# AUDIO_CODEC.net
KiCad netlist of a schematic drawn in Altium Designer
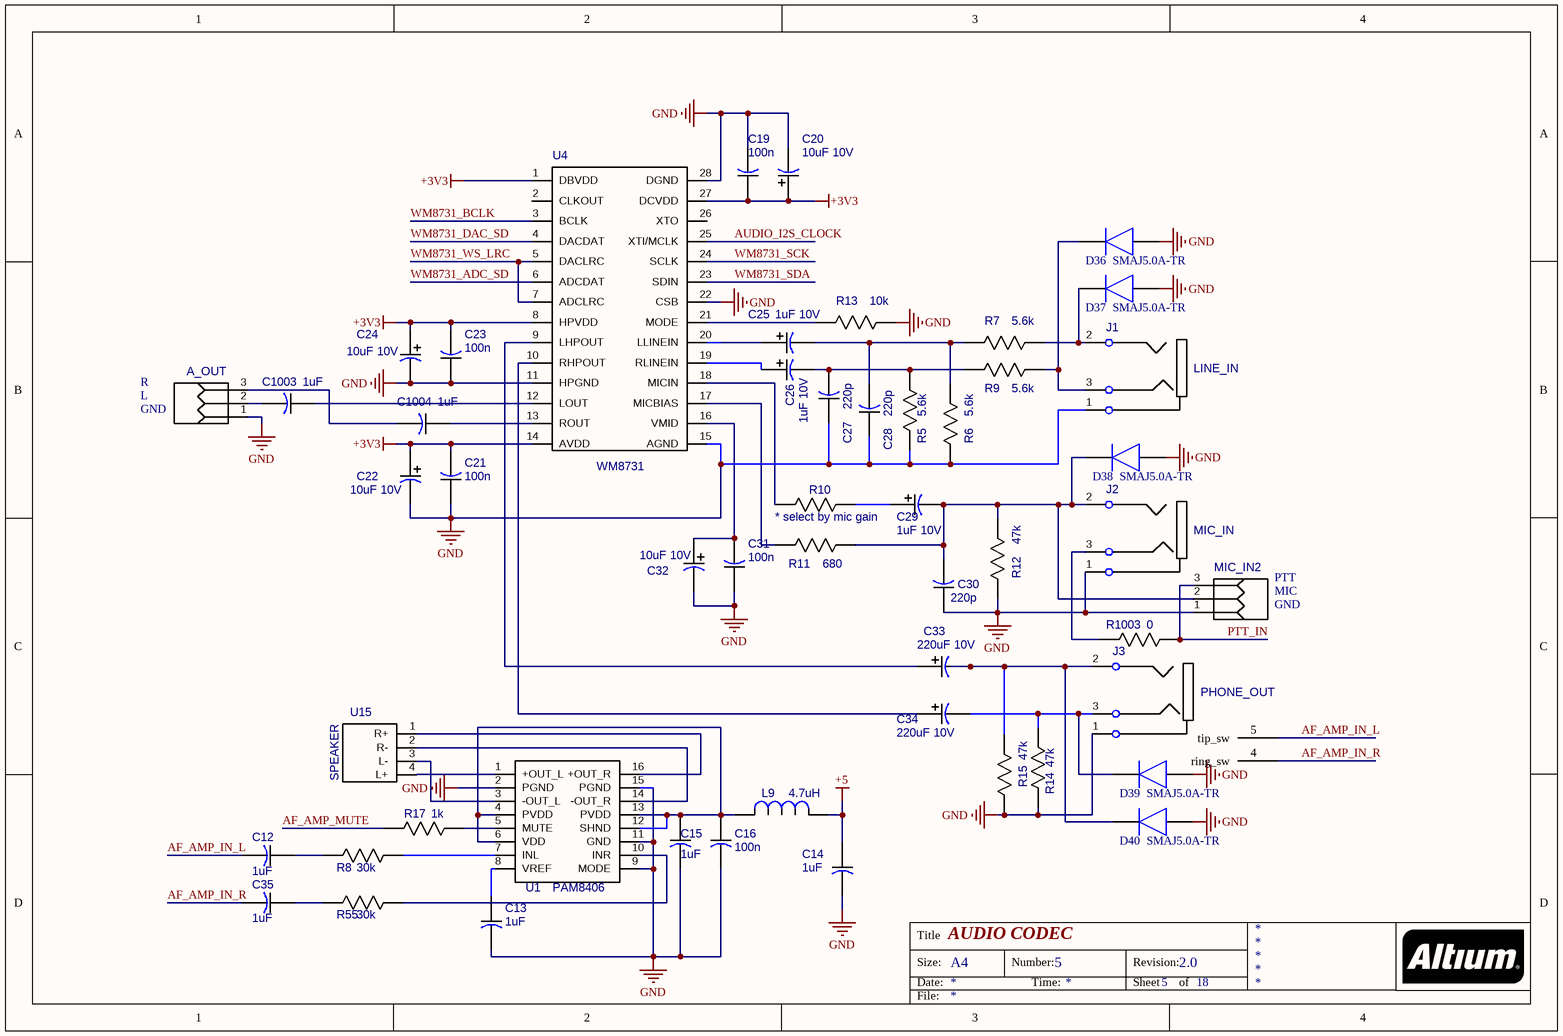
[diagram p0: AUDIO CODEC.SchDoc]

(export (version "E")
  (design (tool "Eeschema 10.0.6"))
  (components
    (comp (ref "A_OUT")
      (value "51022-0300_1")
      (footprint "51022-0200 - duplicate")
      (description "51022-0300")
      (libsource (lib "MOTHERBOARD") (part "51022-0300_1"))
    )
    (comp (ref "C12")
      (value "1uF")
      (footprint "CAP_0805")
      (description "CAP_0805")
      (libsource (lib "*") (part "CAP_0805"))
    )
    (comp (ref "C13")
      (value "1uF")
      (footprint "CAP_0805")
      (description "CAP_0805")
      (libsource (lib "*") (part "CAP_0805"))
    )
    (comp (ref "C14")
      (value "1uF")
      (footprint "CAP_0805")
      (description "CAP_0805")
      (libsource (lib "*") (part "CAP_0805"))
    )
    (comp (ref "C15")
      (value "1uF")
      (footprint "CAP_0805")
      (description "CAP_0805")
      (libsource (lib "*") (part "CAP_0805"))
    )
    (comp (ref "C16")
      (value "100n")
      (footprint "CAP_0805")
      (description "CAP_0805")
      (libsource (lib "*") (part "CAP_0805"))
    )
    (comp (ref "C19")
      (value "100n")
      (footprint "CAP_0805")
      (description "CAP_0805")
      (libsource (lib "*") (part "CAP_0805"))
    )
    (comp (ref "C20")
      (value "10uF 10V")
      (footprint "CAPAE_4.3x4.3h5.4")
      (description "CAPAE_4.3x4.3h5.4")
      (libsource (lib "*") (part "CAPAE_4.3x4.3h5.4"))
    )
    (comp (ref "C21")
      (value "100n")
      (footprint "CAP_0805")
      (description "CAP_0805")
      (libsource (lib "*") (part "CAP_0805"))
    )
    (comp (ref "C22")
      (value "10uF 10V")
      (footprint "CAPAE_4.3x4.3h5.4")
      (description "CAPAE_4.3x4.3h5.4")
      (libsource (lib "*") (part "CAPAE_4.3x4.3h5.4"))
    )
    (comp (ref "C23")
      (value "100n")
      (footprint "CAP_0805")
      (description "CAP_0805")
      (libsource (lib "*") (part "CAP_0805"))
    )
    (comp (ref "C24")
      (value "10uF 10V")
      (footprint "CAPAE_4.3x4.3h5.4")
      (description "CAPAE_4.3x4.3h5.4")
      (libsource (lib "*") (part "CAPAE_4.3x4.3h5.4"))
    )
    (comp (ref "C25")
      (value "1uF 10V")
      (footprint "CAPAE_4.3x4.3h5.4")
      (description "CAPAE_4.3x4.3h5.4")
      (libsource (lib "*") (part "CAPAE_4.3x4.3h5.4"))
    )
    (comp (ref "C26")
      (value "1uF 10V")
      (footprint "CAPAE_4.3x4.3h5.4")
      (description "CAPAE_4.3x4.3h5.4")
      (libsource (lib "*") (part "CAPAE_4.3x4.3h5.4"))
    )
    (comp (ref "C27")
      (value "220p")
      (footprint "CAP_0805")
      (description "CAP_0805")
      (libsource (lib "*") (part "CAP_0805"))
    )
    (comp (ref "C28")
      (value "220p")
      (footprint "CAP_0805")
      (description "CAP_0805")
      (libsource (lib "*") (part "CAP_0805"))
    )
    (comp (ref "C29")
      (value "1uF 10V")
      (footprint "CAPAE_4.3x4.3h5.4")
      (description "CAPAE_4.3x4.3h5.4")
      (libsource (lib "*") (part "CAPAE_4.3x4.3h5.4"))
    )
    (comp (ref "C30")
      (value "220p")
      (footprint "CAP_0805")
      (description "CAP_0805")
      (libsource (lib "*") (part "CAP_0805"))
    )
    (comp (ref "C31")
      (value "100n")
      (footprint "CAP_0805")
      (description "CAP_0805")
      (libsource (lib "*") (part "CAP_0805"))
    )
    (comp (ref "C32")
      (value "10uF 10V")
      (footprint "CAPAE_4.3x4.3h5.4")
      (description "CAPAE_4.3x4.3h5.4")
      (libsource (lib "*") (part "CAPAE_4.3x4.3h5.4"))
    )
    (comp (ref "C33")
      (value "220uF 10V")
      (footprint "EEEFC_sizeС")
      (description "CAPAE_4.3x4.3h5.4")
      (libsource (lib "*") (part "CAPAE_4.3x4.3h5.4"))
    )
    (comp (ref "C34")
      (value "220uF 10V")
      (footprint "EEEFC_sizeС")
      (description "CAPAE_4.3x4.3h5.4")
      (libsource (lib "*") (part "CAPAE_4.3x4.3h5.4"))
    )
    (comp (ref "C35")
      (value "1uF")
      (footprint "CAP_0805")
      (description "CAP_0805")
      (libsource (lib "*") (part "CAP_0805"))
    )
    (comp (ref "C1003")
      (value "1uF")
      (footprint "CAP_0805")
      (description "CAP_0805")
      (libsource (lib "*") (part "CAP_0805"))
    )
    (comp (ref "C1004")
      (value "1uF")
      (footprint "CAP_0805")
      (description "CAP_0805")
      (libsource (lib "*") (part "CAP_0805"))
    )
    (comp (ref "D36")
      (value "SMAJ5.0A-TR")
      (footprint "SamacSys:SMBJ36CATR")
      (description "Diode")
      (fields
        (field (name "MANUFACTURER_PART_NUMBER") "SMLVT3V3")
        (field (name "MOUSER PART NUMBER") "511-SMLVT3V3")
      )
      (libsource (lib "*") (part "SMLVT3V3"))
    )
    (comp (ref "D37")
      (value "SMAJ5.0A-TR")
      (footprint "SamacSys:SMBJ36CATR")
      (description "Diode")
      (fields
        (field (name "MANUFACTURER_PART_NUMBER") "SMLVT3V3")
        (field (name "MOUSER PART NUMBER") "511-SMLVT3V3")
      )
      (libsource (lib "*") (part "SMLVT3V3"))
    )
    (comp (ref "D38")
      (value "SMAJ5.0A-TR")
      (footprint "SamacSys:SMBJ36CATR")
      (description "Diode")
      (fields
        (field (name "MANUFACTURER_PART_NUMBER") "SMLVT3V3")
        (field (name "MOUSER PART NUMBER") "511-SMLVT3V3")
      )
      (libsource (lib "*") (part "SMLVT3V3"))
    )
    (comp (ref "D39")
      (value "SMAJ5.0A-TR")
      (footprint "SamacSys:SMBJ36CATR")
      (description "Diode")
      (fields
        (field (name "MANUFACTURER_PART_NUMBER") "SMLVT3V3")
        (field (name "MOUSER PART NUMBER") "511-SMLVT3V3")
      )
      (libsource (lib "*") (part "SMLVT3V3"))
    )
    (comp (ref "D40")
      (value "SMAJ5.0A-TR")
      (footprint "SamacSys:SMBJ36CATR")
      (description "Diode")
      (fields
        (field (name "MANUFACTURER_PART_NUMBER") "SMLVT3V3")
        (field (name "MOUSER PART NUMBER") "511-SMLVT3V3")
      )
      (libsource (lib "*") (part "SMLVT3V3"))
    )
    (comp (ref "J1")
      (value "LINE_IN")
      (footprint "SJ1-3525NG")
      (description "SJ1-3525NG")
      (libsource (lib "*") (part "SJ1-3523N"))
    )
    (comp (ref "J2")
      (value "MIC_IN")
      (footprint "SJ1-3525NG")
      (description "SJ1-3525NG")
      (libsource (lib "*") (part "SJ1-3523N"))
    )
    (comp (ref "J3")
      (value "PHONE_OUT")
      (footprint "SJ1-3525NG")
      (description "SJ1-3525NG")
      (libsource (lib "") (part "SJ1-3523N_1"))
    )
    (comp (ref "L9")
      (value "4.7uH")
      (footprint "IND_1812")
      (description "IND_1812")
      (fields (field (name "Comment") "3.3uH"))
      (libsource (lib "*") (part "IND_1812"))
    )
    (comp (ref "MIC_IN2")
      (value "51022-0300_1")
      (footprint "51022-0200 - duplicate")
      (description "51022-0300")
      (libsource (lib "MOTHERBOARD") (part "51022-0300_1"))
    )
    (comp (ref "R5")
      (value "5.6k")
      (footprint "RES_0805")
      (description "RES_0805")
      (libsource (lib "*") (part "RES_0805"))
    )
    (comp (ref "R6")
      (value "5.6k")
      (footprint "RES_0805")
      (description "RES_0805")
      (libsource (lib "*") (part "RES_0805"))
    )
    (comp (ref "R7")
      (value "5.6k")
      (footprint "RES_0805")
      (description "RES_0805")
      (libsource (lib "*") (part "RES_0805"))
    )
    (comp (ref "R8")
      (value "30k")
      (footprint "RES_0805")
      (description "RES_0805")
      (libsource (lib "*") (part "RES_0805"))
    )
    (comp (ref "R9")
      (value "5.6k")
      (footprint "RES_0805")
      (description "RES_0805")
      (libsource (lib "*") (part "RES_0805"))
    )
    (comp (ref "R10")
      (value "* select by mic gain")
      (footprint "RES_0805")
      (description "RES_0805")
      (libsource (lib "*") (part "RES_0805"))
    )
    (comp (ref "R11")
      (value "680")
      (footprint "RES_0805")
      (description "RES_0805")
      (libsource (lib "*") (part "RES_0805"))
    )
    (comp (ref "R12")
      (value "47k")
      (footprint "RES_0805")
      (description "RES_0805")
      (libsource (lib "*") (part "RES_0805"))
    )
    (comp (ref "R13")
      (value "10k")
      (footprint "RES_0805")
      (description "RES_0805")
      (libsource (lib "*") (part "RES_0805"))
    )
    (comp (ref "R14")
      (value "47k")
      (footprint "RES_0805")
      (description "RES_0805")
      (libsource (lib "*") (part "RES_0805"))
    )
    (comp (ref "R15")
      (value "47k")
      (footprint "RES_0805")
      (description "RES_0805")
      (libsource (lib "*") (part "RES_0805"))
    )
    (comp (ref "R17")
      (value "1k")
      (footprint "RES_0805")
      (description "RES_0805")
      (libsource (lib "*") (part "RES_0805"))
    )
    (comp (ref "R55")
      (value "30k")
      (footprint "RES_0805")
      (description "RES_0805")
      (libsource (lib "*") (part "RES_0805"))
    )
    (comp (ref "R1003")
      (value "0")
      (footprint "RES_0805")
      (description "RES_0805")
      (libsource (lib "*") (part "RES_0805"))
    )
    (comp (ref "U1") (value "PAM8406") (footprint "PAM8403") (libsource (lib "MOTHERBOARD") (part "PAM8406")))
    (comp (ref "U4") (value "WM8731") (footprint "WM8731") (libsource (lib "*") (part "WM8731")))
    (comp (ref "U15")
      (value "SPEAKER")
      (footprint "speaker conn")
      (description "4 pins conn")
      (libsource (lib "MOTHERBOARD") (part "speaker conn"))
    )
  )
  (nets
    (net (code "1") (name "+3V3") (class "Default")
      (node (ref "C19") (pin "1") (pinfunction "1_1") (pintype "passive"))
      (node (ref "C20") (pin "1") (pinfunction "PLUS_1") (pintype "passive"))
      (node (ref "C21") (pin "2") (pinfunction "2_2") (pintype "passive"))
      (node (ref "C22") (pin "1") (pinfunction "PLUS_1") (pintype "passive"))
      (node (ref "C23") (pin "2") (pinfunction "2_2") (pintype "passive"))
      (node (ref "C24") (pin "1") (pinfunction "PLUS_1") (pintype "passive"))
      (node (ref "U4") (pin "1") (pinfunction "DBVDD_1") (pintype "passive"))
      (node (ref "U4") (pin "14") (pinfunction "AVDD_14") (pintype "passive"))
      (node (ref "U4") (pin "27") (pinfunction "DCVDD_27") (pintype "passive"))
      (node (ref "U4") (pin "8") (pinfunction "HPVDD_8") (pintype "passive"))
    )
    (net (code "2") (name "+5") (class "Default")
      (node (ref "C14") (pin "1") (pinfunction "1_1") (pintype "passive"))
      (node (ref "L9") (pin "2") (pinfunction "2_2") (pintype "passive"))
    )
    (net (code "3") (name "/AF_AMP_IN_L") (class "Default")
      (node (ref "C12") (pin "2") (pinfunction "2_2") (pintype "passive"))
      (node (ref "J3") (pin "5") (pinfunction "tip_sw_5") (pintype "passive"))
    )
    (net (code "4") (name "/AF_AMP_IN_R") (class "Default")
      (node (ref "C35") (pin "2") (pinfunction "2_2") (pintype "passive"))
      (node (ref "J3") (pin "4") (pinfunction "ring_sw_4") (pintype "passive"))
    )
    (net (code "5") (name "/AF_AMP_MUTE") (class "Default")
      (node (ref "R17") (pin "2") (pinfunction "2_2") (pintype "passive"))
    )
    (net (code "6") (name "/AUDIO_I2S_CLOCK") (class "Default")
      (node (ref "U4") (pin "25") (pinfunction "XTI/MCLK_25") (pintype "passive"))
    )
    (net (code "7") (name "/PTT_IN") (class "Default")
      (node (ref "MIC_IN2") (pin "3") (pintype "passive"))
      (node (ref "R1003") (pin "2") (pinfunction "2_2") (pintype "passive"))
    )
    (net (code "8") (name "/WM8731_ADC_SD") (class "Default")
      (node (ref "U4") (pin "6") (pinfunction "ADCDAT_6") (pintype "passive"))
    )
    (net (code "9") (name "/WM8731_BCLK") (class "Default")
      (node (ref "U4") (pin "3") (pinfunction "BCLK_3") (pintype "passive"))
    )
    (net (code "10") (name "/WM8731_DAC_SD") (class "Default")
      (node (ref "U4") (pin "4") (pinfunction "DACDAT_4") (pintype "passive"))
    )
    (net (code "11") (name "/WM8731_SCK") (class "Default")
      (node (ref "U4") (pin "24") (pinfunction "SCLK_24") (pintype "passive"))
    )
    (net (code "12") (name "/WM8731_SDA") (class "Default")
      (node (ref "U4") (pin "23") (pinfunction "SDIN_23") (pintype "passive"))
    )
    (net (code "13") (name "/WM8731_WS_LRC") (class "Default")
      (node (ref "U4") (pin "5") (pinfunction "DACLRC_5") (pintype "passive"))
      (node (ref "U4") (pin "7") (pinfunction "ADCLRC_7") (pintype "passive"))
    )
    (net (code "14") (name "GND") (class "Default")
      (node (ref "A_OUT") (pin "1") (pintype "passive"))
      (node (ref "C13") (pin "2") (pinfunction "2_2") (pintype "passive"))
      (node (ref "C14") (pin "2") (pinfunction "2_2") (pintype "passive"))
      (node (ref "C15") (pin "2") (pinfunction "2_2") (pintype "passive"))
      (node (ref "C16") (pin "2") (pinfunction "2_2") (pintype "passive"))
      (node (ref "C19") (pin "2") (pinfunction "2_2") (pintype "passive"))
      (node (ref "C20") (pin "2") (pinfunction "MINUS_2") (pintype "passive"))
      (node (ref "C21") (pin "1") (pinfunction "1_1") (pintype "passive"))
      (node (ref "C22") (pin "2") (pinfunction "MINUS_2") (pintype "passive"))
      (node (ref "C23") (pin "1") (pinfunction "1_1") (pintype "passive"))
      (node (ref "C24") (pin "2") (pinfunction "MINUS_2") (pintype "passive"))
      (node (ref "C27") (pin "1") (pinfunction "1_1") (pintype "passive"))
      (node (ref "C28") (pin "1") (pinfunction "1_1") (pintype "passive"))
      (node (ref "C30") (pin "1") (pinfunction "1_1") (pintype "passive"))
      (node (ref "C31") (pin "1") (pinfunction "1_1") (pintype "passive"))
      (node (ref "C32") (pin "2") (pinfunction "MINUS_2") (pintype "passive"))
      (node (ref "D36") (pin "2") (pinfunction "A_2") (pintype "passive"))
      (node (ref "D37") (pin "2") (pinfunction "A_2") (pintype "passive"))
      (node (ref "D38") (pin "2") (pinfunction "A_2") (pintype "passive"))
      (node (ref "D39") (pin "2") (pinfunction "A_2") (pintype "passive"))
      (node (ref "D40") (pin "2") (pinfunction "A_2") (pintype "passive"))
      (node (ref "J1") (pin "1") (pinfunction "sleeve_1") (pintype "passive"))
      (node (ref "J2") (pin "1") (pinfunction "sleeve_1") (pintype "passive"))
      (node (ref "J3") (pin "1") (pinfunction "sleeve_1") (pintype "passive"))
      (node (ref "MIC_IN2") (pin "1") (pintype "passive"))
      (node (ref "R12") (pin "1") (pinfunction "1_1") (pintype "passive"))
      (node (ref "R13") (pin "1") (pinfunction "1_1") (pintype "passive"))
      (node (ref "R14") (pin "1") (pinfunction "1_1") (pintype "passive"))
      (node (ref "R15") (pin "1") (pinfunction "1_1") (pintype "passive"))
      (node (ref "R5") (pin "1") (pinfunction "1_1") (pintype "passive"))
      (node (ref "R6") (pin "1") (pinfunction "1_1") (pintype "passive"))
      (node (ref "U1") (pin "11") (pinfunction "GND_11") (pintype "passive"))
      (node (ref "U1") (pin "15") (pinfunction "PGND_15") (pintype "passive"))
      (node (ref "U1") (pin "2") (pinfunction "PGND_2") (pintype "passive"))
      (node (ref "U1") (pin "9") (pinfunction "MODE_9") (pintype "passive"))
      (node (ref "U4") (pin "11") (pinfunction "HPGND_11") (pintype "passive"))
      (node (ref "U4") (pin "15") (pinfunction "AGND_15") (pintype "passive"))
      (node (ref "U4") (pin "22") (pinfunction "CSB_22") (pintype "passive"))
      (node (ref "U4") (pin "28") (pinfunction "DGND_28") (pintype "passive"))
    )
    (net (code "15") (name "Net-(A_OUT-Pad2)") (class "Default")
      (node (ref "A_OUT") (pin "2") (pintype "passive"))
      (node (ref "C1003") (pin "2") (pinfunction "2_2") (pintype "passive"))
    )
    (net (code "16") (name "Net-(A_OUT-Pad3)") (class "Default")
      (node (ref "A_OUT") (pin "3") (pintype "passive"))
      (node (ref "C1004") (pin "2") (pinfunction "2_2") (pintype "passive"))
    )
    (net (code "17") (name "Net-(C12-Pad1)") (class "Default")
      (node (ref "C12") (pin "1") (pinfunction "1_1") (pintype "passive"))
      (node (ref "R8") (pin "2") (pinfunction "2_2") (pintype "passive"))
    )
    (net (code "18") (name "Net-(C25-MINUS)") (class "Default")
      (node (ref "C25") (pin "2") (pinfunction "MINUS_2") (pintype "passive"))
      (node (ref "C28") (pin "2") (pinfunction "2_2") (pintype "passive"))
      (node (ref "R6") (pin "2") (pinfunction "2_2") (pintype "passive"))
      (node (ref "R7") (pin "2") (pinfunction "2_2") (pintype "passive"))
    )
    (net (code "19") (name "Net-(C25-PLUS)") (class "Default")
      (node (ref "C25") (pin "1") (pinfunction "PLUS_1") (pintype "passive"))
      (node (ref "U4") (pin "20") (pinfunction "LLINEIN_20") (pintype "passive"))
    )
    (net (code "20") (name "Net-(C26-MINUS)") (class "Default")
      (node (ref "C26") (pin "2") (pinfunction "MINUS_2") (pintype "passive"))
      (node (ref "C27") (pin "2") (pinfunction "2_2") (pintype "passive"))
      (node (ref "R5") (pin "2") (pinfunction "2_2") (pintype "passive"))
      (node (ref "R9") (pin "2") (pinfunction "2_2") (pintype "passive"))
    )
    (net (code "21") (name "Net-(C26-PLUS)") (class "Default")
      (node (ref "C26") (pin "1") (pinfunction "PLUS_1") (pintype "passive"))
      (node (ref "U4") (pin "19") (pinfunction "RLINEIN_19") (pintype "passive"))
    )
    (net (code "22") (name "Net-(C29-MINUS)") (class "Default")
      (node (ref "C29") (pin "2") (pinfunction "MINUS_2") (pintype "passive"))
      (node (ref "C30") (pin "2") (pinfunction "2_2") (pintype "passive"))
      (node (ref "D38") (pin "1") (pinfunction "K_1") (pintype "passive"))
      (node (ref "J2") (pin "2") (pinfunction "tip_2") (pintype "passive"))
      (node (ref "MIC_IN2") (pin "2") (pintype "passive"))
      (node (ref "R11") (pin "1") (pinfunction "1_1") (pintype "passive"))
      (node (ref "R12") (pin "2") (pinfunction "2_2") (pintype "passive"))
    )
    (net (code "23") (name "Net-(C29-PLUS)") (class "Default")
      (node (ref "C29") (pin "1") (pinfunction "PLUS_1") (pintype "passive"))
      (node (ref "R10") (pin "1") (pinfunction "1_1") (pintype "passive"))
    )
    (net (code "24") (name "Net-(C32-PLUS)") (class "Default")
      (node (ref "C31") (pin "2") (pinfunction "2_2") (pintype "passive"))
      (node (ref "C32") (pin "1") (pinfunction "PLUS_1") (pintype "passive"))
      (node (ref "U4") (pin "16") (pinfunction "VMID_16") (pintype "passive"))
    )
    (net (code "25") (name "Net-(C33-MINUS)") (class "Default")
      (node (ref "C33") (pin "2") (pinfunction "MINUS_2") (pintype "passive"))
      (node (ref "D40") (pin "1") (pinfunction "K_1") (pintype "passive"))
      (node (ref "J3") (pin "2") (pinfunction "tip_2") (pintype "passive"))
      (node (ref "R15") (pin "2") (pinfunction "2_2") (pintype "passive"))
    )
    (net (code "26") (name "Net-(C33-PLUS)") (class "Default")
      (node (ref "C33") (pin "1") (pinfunction "PLUS_1") (pintype "passive"))
      (node (ref "U4") (pin "9") (pinfunction "LHPOUT_9") (pintype "passive"))
    )
    (net (code "27") (name "Net-(C34-MINUS)") (class "Default")
      (node (ref "C34") (pin "2") (pinfunction "MINUS_2") (pintype "passive"))
      (node (ref "D39") (pin "1") (pinfunction "K_1") (pintype "passive"))
      (node (ref "J3") (pin "3") (pinfunction "ring_3") (pintype "passive"))
      (node (ref "R14") (pin "2") (pinfunction "2_2") (pintype "passive"))
    )
    (net (code "28") (name "Net-(C34-PLUS)") (class "Default")
      (node (ref "C34") (pin "1") (pinfunction "PLUS_1") (pintype "passive"))
      (node (ref "U4") (pin "10") (pinfunction "RHPOUT_10") (pintype "passive"))
    )
    (net (code "29") (name "Net-(C35-Pad1)") (class "Default")
      (node (ref "C35") (pin "1") (pinfunction "1_1") (pintype "passive"))
      (node (ref "R55") (pin "2") (pinfunction "2_2") (pintype "passive"))
    )
    (net (code "30") (name "Net-(D36-K)") (class "Default")
      (node (ref "D36") (pin "1") (pinfunction "K_1") (pintype "passive"))
      (node (ref "J1") (pin "3") (pinfunction "ring_3") (pintype "passive"))
      (node (ref "R9") (pin "1") (pinfunction "1_1") (pintype "passive"))
    )
    (net (code "31") (name "Net-(D37-K)") (class "Default")
      (node (ref "D37") (pin "1") (pinfunction "K_1") (pintype "passive"))
      (node (ref "J1") (pin "2") (pinfunction "tip_2") (pintype "passive"))
      (node (ref "R7") (pin "1") (pinfunction "1_1") (pintype "passive"))
    )
    (net (code "32") (name "Net-(J2-ring)") (class "Default")
      (node (ref "J2") (pin "3") (pinfunction "ring_3") (pintype "passive"))
      (node (ref "R1003") (pin "1") (pinfunction "1_1") (pintype "passive"))
    )
    (net (code "33") (name "Net-(U1-+OUT_L)") (class "Default")
      (node (ref "U1") (pin "1") (pinfunction "+OUT_L_1") (pintype "passive"))
      (node (ref "U15") (pin "4") (pinfunction "L+_4") (pintype "passive"))
    )
    (net (code "34") (name "Net-(U1-+OUT_R)") (class "Default")
      (node (ref "U1") (pin "16") (pinfunction "+OUT_R_16") (pintype "passive"))
      (node (ref "U15") (pin "1") (pinfunction "R+_1") (pintype "passive"))
    )
    (net (code "35") (name "Net-(U1--OUT_L)") (class "Default")
      (node (ref "U1") (pin "3") (pinfunction "-OUT_L_3") (pintype "passive"))
      (node (ref "U15") (pin "3") (pinfunction "L-_3") (pintype "passive"))
    )
    (net (code "36") (name "Net-(U1--OUT_R)") (class "Default")
      (node (ref "U1") (pin "14") (pinfunction "-OUT_R_14") (pintype "passive"))
      (node (ref "U15") (pin "2") (pinfunction "R-_2") (pintype "passive"))
    )
    (net (code "37") (name "Net-(U1-INL)") (class "Default")
      (node (ref "R8") (pin "1") (pinfunction "1_1") (pintype "passive"))
      (node (ref "U1") (pin "7") (pinfunction "INL_7") (pintype "passive"))
    )
    (net (code "38") (name "Net-(U1-INR)") (class "Default")
      (node (ref "R55") (pin "1") (pinfunction "1_1") (pintype "passive"))
      (node (ref "U1") (pin "10") (pinfunction "INR_10") (pintype "passive"))
    )
    (net (code "39") (name "Net-(U1-MUTE)") (class "Default")
      (node (ref "R17") (pin "1") (pinfunction "1_1") (pintype "passive"))
      (node (ref "U1") (pin "5") (pinfunction "MUTE_5") (pintype "passive"))
    )
    (net (code "40") (name "Net-(U1-SHND)") (class "Default")
      (node (ref "C15") (pin "1") (pinfunction "1_1") (pintype "passive"))
      (node (ref "C16") (pin "1") (pinfunction "1_1") (pintype "passive"))
      (node (ref "L9") (pin "1") (pinfunction "1_1") (pintype "passive"))
      (node (ref "U1") (pin "12") (pinfunction "SHND_12") (pintype "passive"))
      (node (ref "U1") (pin "13") (pinfunction "PVDD_13") (pintype "passive"))
      (node (ref "U1") (pin "4") (pinfunction "PVDD_4") (pintype "passive"))
      (node (ref "U1") (pin "6") (pinfunction "VDD_6") (pintype "passive"))
    )
    (net (code "41") (name "Net-(U1-VREF)") (class "Default")
      (node (ref "C13") (pin "1") (pinfunction "1_1") (pintype "passive"))
      (node (ref "U1") (pin "8") (pinfunction "VREF_8") (pintype "passive"))
    )
    (net (code "42") (name "Net-(U4-LOUT)") (class "Default")
      (node (ref "C1003") (pin "1") (pinfunction "1_1") (pintype "passive"))
      (node (ref "U4") (pin "12") (pinfunction "LOUT_12") (pintype "passive"))
    )
    (net (code "43") (name "Net-(U4-MICBIAS)") (class "Default")
      (node (ref "R11") (pin "2") (pinfunction "2_2") (pintype "passive"))
      (node (ref "U4") (pin "17") (pinfunction "MICBIAS_17") (pintype "passive"))
    )
    (net (code "44") (name "Net-(U4-MICIN)") (class "Default")
      (node (ref "R10") (pin "2") (pinfunction "2_2") (pintype "passive"))
      (node (ref "U4") (pin "18") (pinfunction "MICIN_18") (pintype "passive"))
    )
    (net (code "45") (name "Net-(U4-MODE)") (class "Default")
      (node (ref "R13") (pin "2") (pinfunction "2_2") (pintype "passive"))
      (node (ref "U4") (pin "21") (pinfunction "MODE_21") (pintype "passive"))
    )
    (net (code "46") (name "Net-(U4-ROUT)") (class "Default")
      (node (ref "C1004") (pin "1") (pinfunction "1_1") (pintype "passive"))
      (node (ref "U4") (pin "13") (pinfunction "ROUT_13") (pintype "passive"))
    )
    (net (code "47") (name "unconnected-(U4-CLKOUT-Pad2)") (class "Default")
      (node (ref "U4") (pin "2") (pinfunction "CLKOUT_2") (pintype "passive"))
    )
    (net (code "48") (name "unconnected-(U4-XTO-Pad26)") (class "Default")
      (node (ref "U4") (pin "26") (pinfunction "XTO_26") (pintype "passive"))
    )
  )
)
